# HydraNFC_Antenna_v1_0.net
KiCad netlist of a schematic drawn in EAGLE
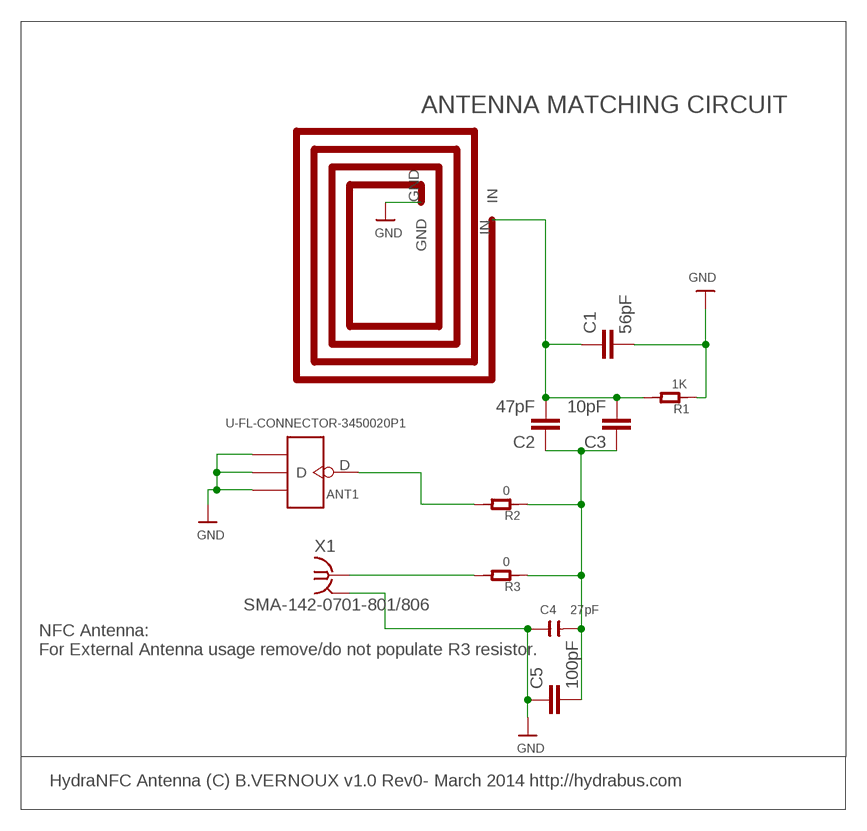
[diagram p0: schematic, sheet 1]

(export (version "E")
  (design (tool "Eeschema 10.0.6"))
  (components
    (comp (ref "ANT1")
      (value "U-FL-CONNECTOR-3450020P1")
      (footprint "eagle-import:U-FL")
      (libsource (lib "eagle-import") (part "U-FL-CONNECTOR-3450020P1"))
    )
    (comp (ref "C1")
      (value "56pF")
      (footprint "eagle-import:C805")
      (libsource (lib "eagle-import") (part "CAPC805"))
    )
    (comp (ref "C2")
      (value "47pF")
      (footprint "eagle-import:C805")
      (libsource (lib "eagle-import") (part "CAPC805"))
    )
    (comp (ref "C3")
      (value "10pF")
      (footprint "eagle-import:C805")
      (libsource (lib "eagle-import") (part "CAPC805"))
    )
    (comp (ref "C4")
      (value "27pF")
      (footprint "eagle-import:C0603")
      (libsource (lib "eagle-import") (part "C-0603"))
    )
    (comp (ref "C5")
      (value "100pF")
      (footprint "eagle-import:C805")
      (libsource (lib "eagle-import") (part "CAPC805"))
    )
    (comp (ref "R1")
      (value "1K")
      (footprint "eagle-import:R0603")
      (libsource (lib "eagle-import") (part "R-0603"))
    )
    (comp (ref "R2")
      (value "0")
      (footprint "eagle-import:R0603")
      (libsource (lib "eagle-import") (part "R-0603"))
    )
    (comp (ref "R3")
      (value "0")
      (footprint "eagle-import:R0603")
      (libsource (lib "eagle-import") (part "R-0603"))
    )
    (comp (ref "U$43")
      (value "NFC_13_56MHz_ANTENNA")
      (footprint "eagle-import:TRF7970A_ANTENNA")
      (libsource (lib "eagle-import") (part "TRF7970A_ANTENNA"))
    )
    (comp (ref "X1")
      (value "SMA-142-0701-801/806")
      (footprint "eagle-import:J502-ND-142-0701-801_806")
      (fields (field (name "MF") "JOHNSON COMPONENTS") (field (name "MPN") "142-0701-801"))
      (libsource (lib "eagle-import") (part "SMA-142-0701-801/806"))
    )
  )
  (nets
    (net (code "1") (name "GND") (class "Default")
      (node (ref "ANT1") (pin "GND1") (pinfunction "GND1_GND1") (pintype "bidirectional"))
      (node (ref "ANT1") (pin "GND2") (pinfunction "GND2_GND2") (pintype "bidirectional"))
      (node (ref "ANT1") (pin "GND3") (pinfunction "GND3_GND3") (pintype "bidirectional"))
      (node (ref "C1") (pin "2") (pinfunction "2_2") (pintype "passive"))
      (node (ref "C4") (pin "2") (pinfunction "2_2") (pintype "bidirectional"))
      (node (ref "C5") (pin "1") (pinfunction "1_1") (pintype "passive"))
      (node (ref "R1") (pin "2") (pinfunction "2_2") (pintype "bidirectional"))
      (node (ref "U$43") (pin "GND") (pinfunction "GND_GND") (pintype "bidirectional"))
      (node (ref "X1") (pin "G@1") (pinfunction "GND_G@1") (pintype "power_in"))
    )
    (net (code "2") (name "Net-(ANT1-PadD)") (class "Default")
      (node (ref "ANT1") (pin "D") (pinfunction "D_D") (pintype "bidirectional"))
      (node (ref "R2") (pin "1") (pinfunction "1_1") (pintype "bidirectional"))
    )
    (net (code "3") (name "Net-(C1-Pad1)") (class "Default")
      (node (ref "C1") (pin "1") (pinfunction "1_1") (pintype "passive"))
      (node (ref "C2") (pin "2") (pinfunction "2_2") (pintype "passive"))
      (node (ref "C3") (pin "2") (pinfunction "2_2") (pintype "passive"))
      (node (ref "R1") (pin "1") (pinfunction "1_1") (pintype "bidirectional"))
      (node (ref "U$43") (pin "IN") (pinfunction "IN_IN") (pintype "bidirectional"))
    )
    (net (code "4") (name "Net-(C2-Pad1)") (class "Default")
      (node (ref "C2") (pin "1") (pinfunction "1_1") (pintype "passive"))
      (node (ref "C3") (pin "1") (pinfunction "1_1") (pintype "passive"))
      (node (ref "C4") (pin "1") (pinfunction "1_1") (pintype "bidirectional"))
      (node (ref "C5") (pin "2") (pinfunction "2_2") (pintype "passive"))
      (node (ref "R2") (pin "2") (pinfunction "2_2") (pintype "bidirectional"))
      (node (ref "R3") (pin "2") (pinfunction "2_2") (pintype "bidirectional"))
    )
    (net (code "5") (name "Net-(R3-Pad1)") (class "Default")
      (node (ref "R3") (pin "1") (pinfunction "1_1") (pintype "bidirectional"))
      (node (ref "X1") (pin "1") (pinfunction "1_1") (pintype "passive"))
    )
  )
)
